# DigitalInput.net
KiCad netlist of a schematic drawn in Altium Designer
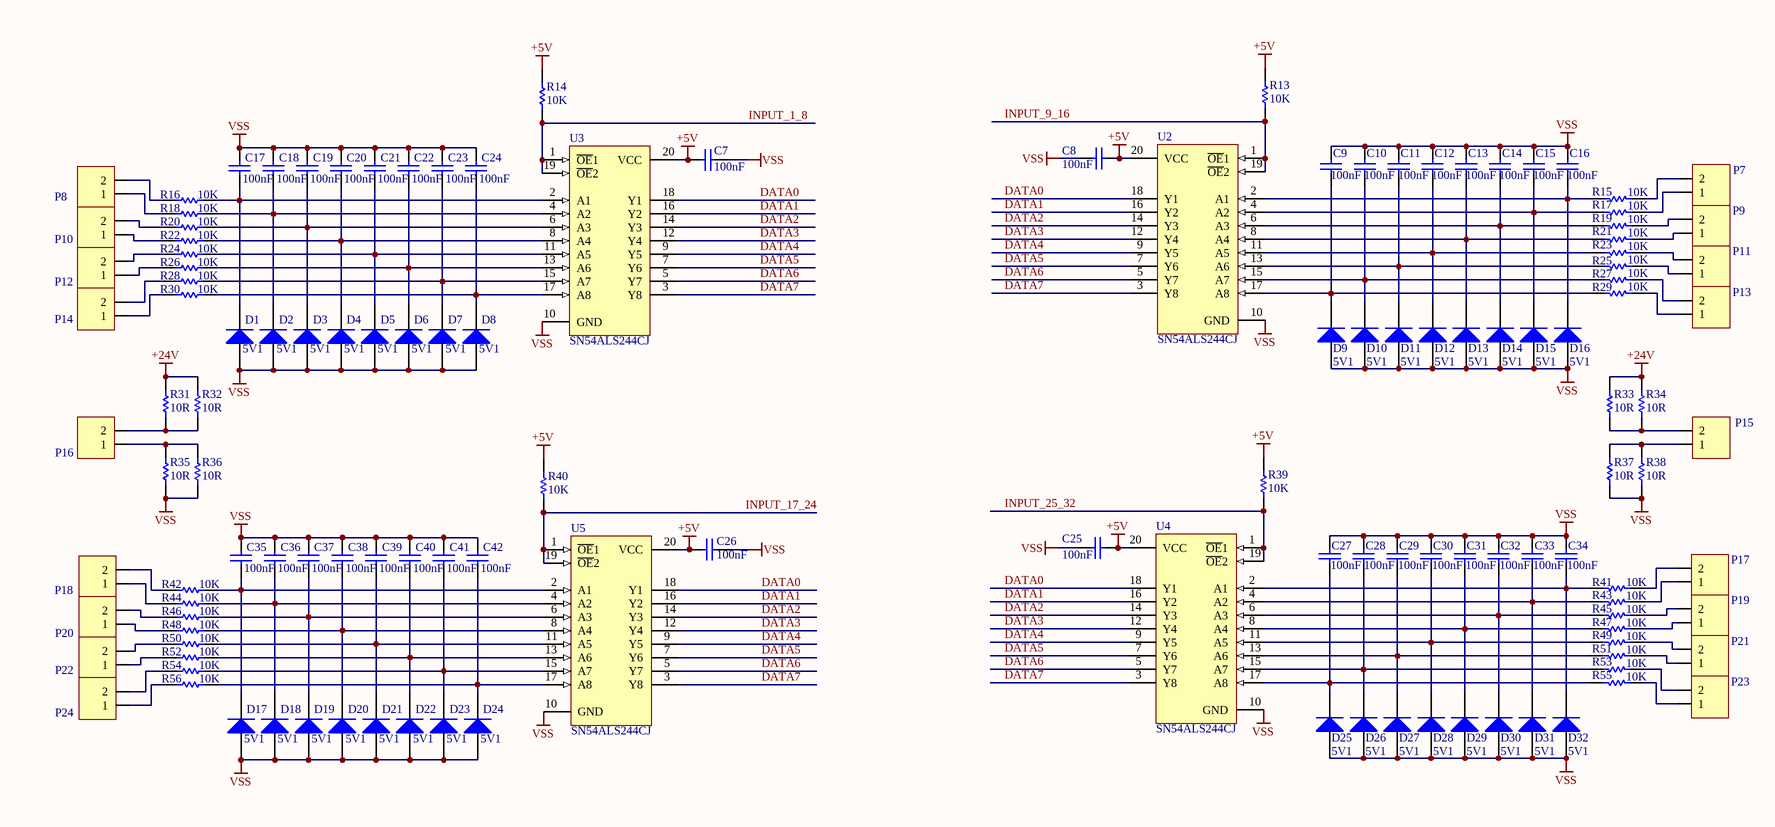
[diagram p0: DigitalInput.SchDoc]

(export (version "E")
  (design (tool "Eeschema 10.0.6"))
  (components
    (comp (ref "C7")
      (value "100nF")
      (footprint "1206")
      (description "Ceramic Chip Capacitor - Standard")
      (fields (field (name "PUBLISHER") "Altium Limited"))
      (libsource (lib "KEMET Chip Capacitor") (part "C1206"))
    )
    (comp (ref "C8")
      (value "100nF")
      (footprint "1206")
      (description "Ceramic Chip Capacitor - Standard")
      (fields (field (name "PUBLISHER") "Altium Limited"))
      (libsource (lib "KEMET Chip Capacitor") (part "C1206"))
    )
    (comp (ref "C9")
      (value "100nF")
      (footprint "1206")
      (description "Ceramic Chip Capacitor - Standard")
      (fields (field (name "PUBLISHER") "Altium Limited"))
      (libsource (lib "KEMET Chip Capacitor") (part "C1206"))
    )
    (comp (ref "C10")
      (value "100nF")
      (footprint "1206")
      (description "Ceramic Chip Capacitor - Standard")
      (fields (field (name "PUBLISHER") "Altium Limited"))
      (libsource (lib "KEMET Chip Capacitor") (part "C1206"))
    )
    (comp (ref "C11")
      (value "100nF")
      (footprint "1206")
      (description "Ceramic Chip Capacitor - Standard")
      (fields (field (name "PUBLISHER") "Altium Limited"))
      (libsource (lib "KEMET Chip Capacitor") (part "C1206"))
    )
    (comp (ref "C12")
      (value "100nF")
      (footprint "1206")
      (description "Ceramic Chip Capacitor - Standard")
      (fields (field (name "PUBLISHER") "Altium Limited"))
      (libsource (lib "KEMET Chip Capacitor") (part "C1206"))
    )
    (comp (ref "C13")
      (value "100nF")
      (footprint "1206")
      (description "Ceramic Chip Capacitor - Standard")
      (fields (field (name "PUBLISHER") "Altium Limited"))
      (libsource (lib "KEMET Chip Capacitor") (part "C1206"))
    )
    (comp (ref "C14")
      (value "100nF")
      (footprint "1206")
      (description "Ceramic Chip Capacitor - Standard")
      (fields (field (name "PUBLISHER") "Altium Limited"))
      (libsource (lib "KEMET Chip Capacitor") (part "C1206"))
    )
    (comp (ref "C15")
      (value "100nF")
      (footprint "1206")
      (description "Ceramic Chip Capacitor - Standard")
      (fields (field (name "PUBLISHER") "Altium Limited"))
      (libsource (lib "KEMET Chip Capacitor") (part "C1206"))
    )
    (comp (ref "C16")
      (value "100nF")
      (footprint "1206")
      (description "Ceramic Chip Capacitor - Standard")
      (fields (field (name "PUBLISHER") "Altium Limited"))
      (libsource (lib "KEMET Chip Capacitor") (part "C1206"))
    )
    (comp (ref "C17")
      (value "100nF")
      (footprint "1206")
      (description "Ceramic Chip Capacitor - Standard")
      (fields (field (name "PUBLISHER") "Altium Limited"))
      (libsource (lib "KEMET Chip Capacitor") (part "C1206"))
    )
    (comp (ref "C18")
      (value "100nF")
      (footprint "1206")
      (description "Ceramic Chip Capacitor - Standard")
      (fields (field (name "PUBLISHER") "Altium Limited"))
      (libsource (lib "KEMET Chip Capacitor") (part "C1206"))
    )
    (comp (ref "C19")
      (value "100nF")
      (footprint "1206")
      (description "Ceramic Chip Capacitor - Standard")
      (fields (field (name "PUBLISHER") "Altium Limited"))
      (libsource (lib "KEMET Chip Capacitor") (part "C1206"))
    )
    (comp (ref "C20")
      (value "100nF")
      (footprint "1206")
      (description "Ceramic Chip Capacitor - Standard")
      (fields (field (name "PUBLISHER") "Altium Limited"))
      (libsource (lib "KEMET Chip Capacitor") (part "C1206"))
    )
    (comp (ref "C21")
      (value "100nF")
      (footprint "1206")
      (description "Ceramic Chip Capacitor - Standard")
      (fields (field (name "PUBLISHER") "Altium Limited"))
      (libsource (lib "KEMET Chip Capacitor") (part "C1206"))
    )
    (comp (ref "C22")
      (value "100nF")
      (footprint "1206")
      (description "Ceramic Chip Capacitor - Standard")
      (fields (field (name "PUBLISHER") "Altium Limited"))
      (libsource (lib "KEMET Chip Capacitor") (part "C1206"))
    )
    (comp (ref "C23")
      (value "100nF")
      (footprint "1206")
      (description "Ceramic Chip Capacitor - Standard")
      (fields (field (name "PUBLISHER") "Altium Limited"))
      (libsource (lib "KEMET Chip Capacitor") (part "C1206"))
    )
    (comp (ref "C24")
      (value "100nF")
      (footprint "1206")
      (description "Ceramic Chip Capacitor - Standard")
      (fields (field (name "PUBLISHER") "Altium Limited"))
      (libsource (lib "KEMET Chip Capacitor") (part "C1206"))
    )
    (comp (ref "C25")
      (value "100nF")
      (footprint "1206")
      (description "Ceramic Chip Capacitor - Standard")
      (fields (field (name "PUBLISHER") "Altium Limited"))
      (libsource (lib "KEMET Chip Capacitor") (part "C1206"))
    )
    (comp (ref "C26")
      (value "100nF")
      (footprint "1206")
      (description "Ceramic Chip Capacitor - Standard")
      (fields (field (name "PUBLISHER") "Altium Limited"))
      (libsource (lib "KEMET Chip Capacitor") (part "C1206"))
    )
    (comp (ref "C27")
      (value "100nF")
      (footprint "1206")
      (description "Ceramic Chip Capacitor - Standard")
      (fields (field (name "PUBLISHER") "Altium Limited"))
      (libsource (lib "KEMET Chip Capacitor") (part "C1206"))
    )
    (comp (ref "C28")
      (value "100nF")
      (footprint "1206")
      (description "Ceramic Chip Capacitor - Standard")
      (fields (field (name "PUBLISHER") "Altium Limited"))
      (libsource (lib "KEMET Chip Capacitor") (part "C1206"))
    )
    (comp (ref "C29")
      (value "100nF")
      (footprint "1206")
      (description "Ceramic Chip Capacitor - Standard")
      (fields (field (name "PUBLISHER") "Altium Limited"))
      (libsource (lib "KEMET Chip Capacitor") (part "C1206"))
    )
    (comp (ref "C30")
      (value "100nF")
      (footprint "1206")
      (description "Ceramic Chip Capacitor - Standard")
      (fields (field (name "PUBLISHER") "Altium Limited"))
      (libsource (lib "KEMET Chip Capacitor") (part "C1206"))
    )
    (comp (ref "C31")
      (value "100nF")
      (footprint "1206")
      (description "Ceramic Chip Capacitor - Standard")
      (fields (field (name "PUBLISHER") "Altium Limited"))
      (libsource (lib "KEMET Chip Capacitor") (part "C1206"))
    )
    (comp (ref "C32")
      (value "100nF")
      (footprint "1206")
      (description "Ceramic Chip Capacitor - Standard")
      (fields (field (name "PUBLISHER") "Altium Limited"))
      (libsource (lib "KEMET Chip Capacitor") (part "C1206"))
    )
    (comp (ref "C33")
      (value "100nF")
      (footprint "1206")
      (description "Ceramic Chip Capacitor - Standard")
      (fields (field (name "PUBLISHER") "Altium Limited"))
      (libsource (lib "KEMET Chip Capacitor") (part "C1206"))
    )
    (comp (ref "C34")
      (value "100nF")
      (footprint "1206")
      (description "Ceramic Chip Capacitor - Standard")
      (fields (field (name "PUBLISHER") "Altium Limited"))
      (libsource (lib "KEMET Chip Capacitor") (part "C1206"))
    )
    (comp (ref "C35")
      (value "100nF")
      (footprint "1206")
      (description "Ceramic Chip Capacitor - Standard")
      (fields (field (name "PUBLISHER") "Altium Limited"))
      (libsource (lib "KEMET Chip Capacitor") (part "C1206"))
    )
    (comp (ref "C36")
      (value "100nF")
      (footprint "1206")
      (description "Ceramic Chip Capacitor - Standard")
      (fields (field (name "PUBLISHER") "Altium Limited"))
      (libsource (lib "KEMET Chip Capacitor") (part "C1206"))
    )
    (comp (ref "C37")
      (value "100nF")
      (footprint "1206")
      (description "Ceramic Chip Capacitor - Standard")
      (fields (field (name "PUBLISHER") "Altium Limited"))
      (libsource (lib "KEMET Chip Capacitor") (part "C1206"))
    )
    (comp (ref "C38")
      (value "100nF")
      (footprint "1206")
      (description "Ceramic Chip Capacitor - Standard")
      (fields (field (name "PUBLISHER") "Altium Limited"))
      (libsource (lib "KEMET Chip Capacitor") (part "C1206"))
    )
    (comp (ref "C39")
      (value "100nF")
      (footprint "1206")
      (description "Ceramic Chip Capacitor - Standard")
      (fields (field (name "PUBLISHER") "Altium Limited"))
      (libsource (lib "KEMET Chip Capacitor") (part "C1206"))
    )
    (comp (ref "C40")
      (value "100nF")
      (footprint "1206")
      (description "Ceramic Chip Capacitor - Standard")
      (fields (field (name "PUBLISHER") "Altium Limited"))
      (libsource (lib "KEMET Chip Capacitor") (part "C1206"))
    )
    (comp (ref "C41")
      (value "100nF")
      (footprint "1206")
      (description "Ceramic Chip Capacitor - Standard")
      (fields (field (name "PUBLISHER") "Altium Limited"))
      (libsource (lib "KEMET Chip Capacitor") (part "C1206"))
    )
    (comp (ref "C42")
      (value "100nF")
      (footprint "1206")
      (description "Ceramic Chip Capacitor - Standard")
      (fields (field (name "PUBLISHER") "Altium Limited"))
      (libsource (lib "KEMET Chip Capacitor") (part "C1206"))
    )
    (comp (ref "D1")
      (value "5V1")
      (footprint "SOD80C")
      (description "Voltage Regulator Diode")
      (fields (field (name "PUBLISHER") "Altium Limited"))
      (libsource (lib "Philips Discrete Diode - Switching") (part "BZV85-C5V1"))
    )
    (comp (ref "D2")
      (value "5V1")
      (footprint "SOD80C")
      (description "Voltage Regulator Diode")
      (fields (field (name "PUBLISHER") "Altium Limited"))
      (libsource (lib "Philips Discrete Diode - Switching") (part "BZV85-C5V1"))
    )
    (comp (ref "D3")
      (value "5V1")
      (footprint "SOD80C")
      (description "Voltage Regulator Diode")
      (fields (field (name "PUBLISHER") "Altium Limited"))
      (libsource (lib "Philips Discrete Diode - Switching") (part "BZV85-C5V1"))
    )
    (comp (ref "D4")
      (value "5V1")
      (footprint "SOD80C")
      (description "Voltage Regulator Diode")
      (fields (field (name "PUBLISHER") "Altium Limited"))
      (libsource (lib "Philips Discrete Diode - Switching") (part "BZV85-C5V1"))
    )
    (comp (ref "D5")
      (value "5V1")
      (footprint "SOD80C")
      (description "Voltage Regulator Diode")
      (fields (field (name "PUBLISHER") "Altium Limited"))
      (libsource (lib "Philips Discrete Diode - Switching") (part "BZV85-C5V1"))
    )
    (comp (ref "D6")
      (value "5V1")
      (footprint "SOD80C")
      (description "Voltage Regulator Diode")
      (fields (field (name "PUBLISHER") "Altium Limited"))
      (libsource (lib "Philips Discrete Diode - Switching") (part "BZV85-C5V1"))
    )
    (comp (ref "D7")
      (value "5V1")
      (footprint "SOD80C")
      (description "Voltage Regulator Diode")
      (fields (field (name "PUBLISHER") "Altium Limited"))
      (libsource (lib "Philips Discrete Diode - Switching") (part "BZV85-C5V1"))
    )
    (comp (ref "D8")
      (value "5V1")
      (footprint "SOD80C")
      (description "Voltage Regulator Diode")
      (fields (field (name "PUBLISHER") "Altium Limited"))
      (libsource (lib "Philips Discrete Diode - Switching") (part "BZV85-C5V1"))
    )
    (comp (ref "D9")
      (value "5V1")
      (footprint "SOD80C")
      (description "Voltage Regulator Diode")
      (fields (field (name "PUBLISHER") "Altium Limited"))
      (libsource (lib "Philips Discrete Diode - Switching") (part "BZV85-C5V1"))
    )
    (comp (ref "D10")
      (value "5V1")
      (footprint "SOD80C")
      (description "Voltage Regulator Diode")
      (fields (field (name "PUBLISHER") "Altium Limited"))
      (libsource (lib "Philips Discrete Diode - Switching") (part "BZV85-C5V1"))
    )
    (comp (ref "D11")
      (value "5V1")
      (footprint "SOD80C")
      (description "Voltage Regulator Diode")
      (fields (field (name "PUBLISHER") "Altium Limited"))
      (libsource (lib "Philips Discrete Diode - Switching") (part "BZV85-C5V1"))
    )
    (comp (ref "D12")
      (value "5V1")
      (footprint "SOD80C")
      (description "Voltage Regulator Diode")
      (fields (field (name "PUBLISHER") "Altium Limited"))
      (libsource (lib "Philips Discrete Diode - Switching") (part "BZV85-C5V1"))
    )
    (comp (ref "D13")
      (value "5V1")
      (footprint "SOD80C")
      (description "Voltage Regulator Diode")
      (fields (field (name "PUBLISHER") "Altium Limited"))
      (libsource (lib "Philips Discrete Diode - Switching") (part "BZV85-C5V1"))
    )
    (comp (ref "D14")
      (value "5V1")
      (footprint "SOD80C")
      (description "Voltage Regulator Diode")
      (fields (field (name "PUBLISHER") "Altium Limited"))
      (libsource (lib "Philips Discrete Diode - Switching") (part "BZV85-C5V1"))
    )
    (comp (ref "D15")
      (value "5V1")
      (footprint "SOD80C")
      (description "Voltage Regulator Diode")
      (fields (field (name "PUBLISHER") "Altium Limited"))
      (libsource (lib "Philips Discrete Diode - Switching") (part "BZV85-C5V1"))
    )
    (comp (ref "D16")
      (value "5V1")
      (footprint "SOD80C")
      (description "Voltage Regulator Diode")
      (fields (field (name "PUBLISHER") "Altium Limited"))
      (libsource (lib "Philips Discrete Diode - Switching") (part "BZV85-C5V1"))
    )
    (comp (ref "D17")
      (value "5V1")
      (footprint "SOD80C")
      (description "Voltage Regulator Diode")
      (fields (field (name "PUBLISHER") "Altium Limited"))
      (libsource (lib "Philips Discrete Diode - Switching") (part "BZV85-C5V1"))
    )
    (comp (ref "D18")
      (value "5V1")
      (footprint "SOD80C")
      (description "Voltage Regulator Diode")
      (fields (field (name "PUBLISHER") "Altium Limited"))
      (libsource (lib "Philips Discrete Diode - Switching") (part "BZV85-C5V1"))
    )
    (comp (ref "D19")
      (value "5V1")
      (footprint "SOD80C")
      (description "Voltage Regulator Diode")
      (fields (field (name "PUBLISHER") "Altium Limited"))
      (libsource (lib "Philips Discrete Diode - Switching") (part "BZV85-C5V1"))
    )
    (comp (ref "D20")
      (value "5V1")
      (footprint "SOD80C")
      (description "Voltage Regulator Diode")
      (fields (field (name "PUBLISHER") "Altium Limited"))
      (libsource (lib "Philips Discrete Diode - Switching") (part "BZV85-C5V1"))
    )
    (comp (ref "D21")
      (value "5V1")
      (footprint "SOD80C")
      (description "Voltage Regulator Diode")
      (fields (field (name "PUBLISHER") "Altium Limited"))
      (libsource (lib "Philips Discrete Diode - Switching") (part "BZV85-C5V1"))
    )
    (comp (ref "D22")
      (value "5V1")
      (footprint "SOD80C")
      (description "Voltage Regulator Diode")
      (fields (field (name "PUBLISHER") "Altium Limited"))
      (libsource (lib "Philips Discrete Diode - Switching") (part "BZV85-C5V1"))
    )
    (comp (ref "D23")
      (value "5V1")
      (footprint "SOD80C")
      (description "Voltage Regulator Diode")
      (fields (field (name "PUBLISHER") "Altium Limited"))
      (libsource (lib "Philips Discrete Diode - Switching") (part "BZV85-C5V1"))
    )
    (comp (ref "D24")
      (value "5V1")
      (footprint "SOD80C")
      (description "Voltage Regulator Diode")
      (fields (field (name "PUBLISHER") "Altium Limited"))
      (libsource (lib "Philips Discrete Diode - Switching") (part "BZV85-C5V1"))
    )
    (comp (ref "D25")
      (value "5V1")
      (footprint "SOD80C")
      (description "Voltage Regulator Diode")
      (fields (field (name "PUBLISHER") "Altium Limited"))
      (libsource (lib "Philips Discrete Diode - Switching") (part "BZV85-C5V1"))
    )
    (comp (ref "D26")
      (value "5V1")
      (footprint "SOD80C")
      (description "Voltage Regulator Diode")
      (fields (field (name "PUBLISHER") "Altium Limited"))
      (libsource (lib "Philips Discrete Diode - Switching") (part "BZV85-C5V1"))
    )
    (comp (ref "D27")
      (value "5V1")
      (footprint "SOD80C")
      (description "Voltage Regulator Diode")
      (fields (field (name "PUBLISHER") "Altium Limited"))
      (libsource (lib "Philips Discrete Diode - Switching") (part "BZV85-C5V1"))
    )
    (comp (ref "D28")
      (value "5V1")
      (footprint "SOD80C")
      (description "Voltage Regulator Diode")
      (fields (field (name "PUBLISHER") "Altium Limited"))
      (libsource (lib "Philips Discrete Diode - Switching") (part "BZV85-C5V1"))
    )
    (comp (ref "D29")
      (value "5V1")
      (footprint "SOD80C")
      (description "Voltage Regulator Diode")
      (fields (field (name "PUBLISHER") "Altium Limited"))
      (libsource (lib "Philips Discrete Diode - Switching") (part "BZV85-C5V1"))
    )
    (comp (ref "D30")
      (value "5V1")
      (footprint "SOD80C")
      (description "Voltage Regulator Diode")
      (fields (field (name "PUBLISHER") "Altium Limited"))
      (libsource (lib "Philips Discrete Diode - Switching") (part "BZV85-C5V1"))
    )
    (comp (ref "D31")
      (value "5V1")
      (footprint "SOD80C")
      (description "Voltage Regulator Diode")
      (fields (field (name "PUBLISHER") "Altium Limited"))
      (libsource (lib "Philips Discrete Diode - Switching") (part "BZV85-C5V1"))
    )
    (comp (ref "D32")
      (value "5V1")
      (footprint "SOD80C")
      (description "Voltage Regulator Diode")
      (fields (field (name "PUBLISHER") "Altium Limited"))
      (libsource (lib "Philips Discrete Diode - Switching") (part "BZV85-C5V1"))
    )
    (comp (ref "P7")
      (value "~")
      (footprint "TERMINAL BLOK 2")
      (description "Terminal blok 2")
      (libsource (lib "") (part "Terminal blok 2 pina_3"))
    )
    (comp (ref "P8")
      (value "~")
      (footprint "TERMINAL BLOK 2")
      (description "Terminal blok 2")
      (libsource (lib "TERMINAL_CONNECOR_2") (part "Terminal blok 2 pina"))
    )
    (comp (ref "P9")
      (value "~")
      (footprint "TERMINAL BLOK 2")
      (description "Terminal blok 2")
      (libsource (lib "") (part "Terminal blok 2 pina_1"))
    )
    (comp (ref "P10")
      (value "~")
      (footprint "TERMINAL BLOK 2")
      (description "Terminal blok 2")
      (libsource (lib "TERMINAL_CONNECOR_2") (part "Terminal blok 2 pina"))
    )
    (comp (ref "P11")
      (value "~")
      (footprint "TERMINAL BLOK 2")
      (description "Terminal blok 2")
      (libsource (lib "") (part "Terminal blok 2 pina_2"))
    )
    (comp (ref "P12")
      (value "~")
      (footprint "TERMINAL BLOK 2")
      (description "Terminal blok 2")
      (libsource (lib "") (part "Terminal blok 2 pina_5"))
    )
    (comp (ref "P13")
      (value "~")
      (footprint "TERMINAL BLOK 2")
      (description "Terminal blok 2")
      (libsource (lib "") (part "Terminal blok 2 pina_2"))
    )
    (comp (ref "P14")
      (value "~")
      (footprint "TERMINAL BLOK 2")
      (description "Terminal blok 2")
      (libsource (lib "") (part "Terminal blok 2 pina_7"))
    )
    (comp (ref "P15")
      (value "~")
      (footprint "TERMINAL BLOK 2")
      (description "Terminal blok 2")
      (libsource (lib "") (part "Terminal blok 2 pina_6"))
    )
    (comp (ref "P16")
      (value "~")
      (footprint "TERMINAL BLOK 2")
      (description "Terminal blok 2")
      (libsource (lib "") (part "Terminal blok 2 pina_8"))
    )
    (comp (ref "P17")
      (value "~")
      (footprint "TERMINAL BLOK 2")
      (description "Terminal blok 2")
      (libsource (lib "") (part "Terminal blok 2 pina_1"))
    )
    (comp (ref "P18")
      (value "~")
      (footprint "TERMINAL BLOK 2")
      (description "Terminal blok 2")
      (libsource (lib "TERMINAL_CONNECOR_2") (part "Terminal blok 2 pina"))
    )
    (comp (ref "P19")
      (value "~")
      (footprint "TERMINAL BLOK 2")
      (description "Terminal blok 2")
      (libsource (lib "") (part "Terminal blok 2 pina_1"))
    )
    (comp (ref "P20")
      (value "~")
      (footprint "TERMINAL BLOK 2")
      (description "Terminal blok 2")
      (libsource (lib "") (part "Terminal blok 2 pina_5"))
    )
    (comp (ref "P21")
      (value "~")
      (footprint "TERMINAL BLOK 2")
      (description "Terminal blok 2")
      (libsource (lib "") (part "Terminal blok 2 pina_2"))
    )
    (comp (ref "P22")
      (value "~")
      (footprint "TERMINAL BLOK 2")
      (description "Terminal blok 2")
      (libsource (lib "") (part "Terminal blok 2 pina_5"))
    )
    (comp (ref "P23")
      (value "~")
      (footprint "TERMINAL BLOK 2")
      (description "Terminal blok 2")
      (libsource (lib "") (part "Terminal blok 2 pina_3"))
    )
    (comp (ref "P24")
      (value "~")
      (footprint "TERMINAL BLOK 2")
      (description "Terminal blok 2")
      (libsource (lib "") (part "Terminal blok 2 pina_4"))
    )
    (comp (ref "R13")
      (value "10K")
      (footprint "ERA-0805")
      (fields (field (name "PUBLISHER") "Altium Limited"))
      (libsource (lib "Panasonic Resistor") (part "ERA6Y"))
    )
    (comp (ref "R14")
      (value "10K")
      (footprint "ERA-0805")
      (fields (field (name "PUBLISHER") "Altium Limited"))
      (libsource (lib "Panasonic Resistor") (part "ERA6Y"))
    )
    (comp (ref "R15")
      (value "10K")
      (footprint "ERA-0805")
      (fields (field (name "PUBLISHER") "Altium Limited"))
      (libsource (lib "Panasonic Resistor") (part "ERA6Y"))
    )
    (comp (ref "R16")
      (value "10K")
      (footprint "ERA-0805")
      (fields (field (name "PUBLISHER") "Altium Limited"))
      (libsource (lib "Panasonic Resistor") (part "ERA6Y"))
    )
    (comp (ref "R17")
      (value "10K")
      (footprint "ERA-0805")
      (fields (field (name "PUBLISHER") "Altium Limited"))
      (libsource (lib "Panasonic Resistor") (part "ERA6Y"))
    )
    (comp (ref "R18")
      (value "10K")
      (footprint "ERA-0805")
      (fields (field (name "PUBLISHER") "Altium Limited"))
      (libsource (lib "Panasonic Resistor") (part "ERA6Y"))
    )
    (comp (ref "R19")
      (value "10K")
      (footprint "ERA-0805")
      (fields (field (name "PUBLISHER") "Altium Limited"))
      (libsource (lib "Panasonic Resistor") (part "ERA6Y"))
    )
    (comp (ref "R20")
      (value "10K")
      (footprint "ERA-0805")
      (fields (field (name "PUBLISHER") "Altium Limited"))
      (libsource (lib "Panasonic Resistor") (part "ERA6Y"))
    )
    (comp (ref "R21")
      (value "10K")
      (footprint "ERA-0805")
      (fields (field (name "PUBLISHER") "Altium Limited"))
      (libsource (lib "Panasonic Resistor") (part "ERA6Y"))
    )
    (comp (ref "R22")
      (value "10K")
      (footprint "ERA-0805")
      (fields (field (name "PUBLISHER") "Altium Limited"))
      (libsource (lib "Panasonic Resistor") (part "ERA6Y"))
    )
    (comp (ref "R23")
      (value "10K")
      (footprint "ERA-0805")
      (fields (field (name "PUBLISHER") "Altium Limited"))
      (libsource (lib "Panasonic Resistor") (part "ERA6Y"))
    )
    (comp (ref "R24")
      (value "10K")
      (footprint "ERA-0805")
      (fields (field (name "PUBLISHER") "Altium Limited"))
      (libsource (lib "Panasonic Resistor") (part "ERA6Y"))
    )
    (comp (ref "R25")
      (value "10K")
      (footprint "ERA-0805")
      (fields (field (name "PUBLISHER") "Altium Limited"))
      (libsource (lib "Panasonic Resistor") (part "ERA6Y"))
    )
    (comp (ref "R26")
      (value "10K")
      (footprint "ERA-0805")
      (fields (field (name "PUBLISHER") "Altium Limited"))
      (libsource (lib "Panasonic Resistor") (part "ERA6Y"))
    )
    (comp (ref "R27")
      (value "10K")
      (footprint "ERA-0805")
      (fields (field (name "PUBLISHER") "Altium Limited"))
      (libsource (lib "Panasonic Resistor") (part "ERA6Y"))
    )
    (comp (ref "R28")
      (value "10K")
      (footprint "ERA-0805")
      (fields (field (name "PUBLISHER") "Altium Limited"))
      (libsource (lib "Panasonic Resistor") (part "ERA6Y"))
    )
    (comp (ref "R29")
      (value "10K")
      (footprint "ERA-0805")
      (fields (field (name "PUBLISHER") "Altium Limited"))
      (libsource (lib "Panasonic Resistor") (part "ERA6Y"))
    )
    (comp (ref "R30")
      (value "10K")
      (footprint "ERA-0805")
      (fields (field (name "PUBLISHER") "Altium Limited"))
      (libsource (lib "Panasonic Resistor") (part "ERA6Y"))
    )
    (comp (ref "R31")
      (value "10R")
      (footprint "ERA-0603")
      (fields (field (name "PUBLISHER") "Altium Limited"))
      (libsource (lib "Panasonic Resistor") (part "ERA3Y"))
    )
    (comp (ref "R32")
      (value "10R")
      (footprint "ERA-0603")
      (fields (field (name "PUBLISHER") "Altium Limited"))
      (libsource (lib "Panasonic Resistor") (part "ERA3Y"))
    )
    (comp (ref "R33")
      (value "10R")
      (footprint "ERA-0603")
      (fields (field (name "PUBLISHER") "Altium Limited"))
      (libsource (lib "Panasonic Resistor") (part "ERA3Y"))
    )
    (comp (ref "R34")
      (value "10R")
      (footprint "ERA-0603")
      (fields (field (name "PUBLISHER") "Altium Limited"))
      (libsource (lib "Panasonic Resistor") (part "ERA3Y"))
    )
    (comp (ref "R35")
      (value "10R")
      (footprint "ERA-0603")
      (fields (field (name "PUBLISHER") "Altium Limited"))
      (libsource (lib "Panasonic Resistor") (part "ERA3Y"))
    )
    (comp (ref "R36")
      (value "10R")
      (footprint "ERA-0603")
      (fields (field (name "PUBLISHER") "Altium Limited"))
      (libsource (lib "Panasonic Resistor") (part "ERA3Y"))
    )
    (comp (ref "R37")
      (value "10R")
      (footprint "ERA-0603")
      (fields (field (name "PUBLISHER") "Altium Limited"))
      (libsource (lib "Panasonic Resistor") (part "ERA3Y"))
    )
    (comp (ref "R38")
      (value "10R")
      (footprint "ERA-0603")
      (fields (field (name "PUBLISHER") "Altium Limited"))
      (libsource (lib "Panasonic Resistor") (part "ERA3Y"))
    )
    (comp (ref "R39")
      (value "10K")
      (footprint "ERA-0805")
      (fields (field (name "PUBLISHER") "Altium Limited"))
      (libsource (lib "Panasonic Resistor") (part "ERA6Y"))
    )
    (comp (ref "R40")
      (value "10K")
      (footprint "ERA-0805")
      (fields (field (name "PUBLISHER") "Altium Limited"))
      (libsource (lib "Panasonic Resistor") (part "ERA6Y"))
    )
    (comp (ref "R41")
      (value "10K")
      (footprint "ERA-0805")
      (fields (field (name "PUBLISHER") "Altium Limited"))
      (libsource (lib "Panasonic Resistor") (part "ERA6Y"))
    )
    (comp (ref "R42")
      (value "10K")
      (footprint "ERA-0805")
      (fields (field (name "PUBLISHER") "Altium Limited"))
      (libsource (lib "Panasonic Resistor") (part "ERA6Y"))
    )
    (comp (ref "R43")
      (value "10K")
      (footprint "ERA-0805")
      (fields (field (name "PUBLISHER") "Altium Limited"))
      (libsource (lib "Panasonic Resistor") (part "ERA6Y"))
    )
    (comp (ref "R44")
      (value "10K")
      (footprint "ERA-0805")
      (fields (field (name "PUBLISHER") "Altium Limited"))
      (libsource (lib "Panasonic Resistor") (part "ERA6Y"))
    )
    (comp (ref "R45")
      (value "10K")
      (footprint "ERA-0805")
      (fields (field (name "PUBLISHER") "Altium Limited"))
      (libsource (lib "Panasonic Resistor") (part "ERA6Y"))
    )
    (comp (ref "R46")
      (value "10K")
      (footprint "ERA-0805")
      (fields (field (name "PUBLISHER") "Altium Limited"))
      (libsource (lib "Panasonic Resistor") (part "ERA6Y"))
    )
    (comp (ref "R47")
      (value "10K")
      (footprint "ERA-0805")
      (fields (field (name "PUBLISHER") "Altium Limited"))
      (libsource (lib "Panasonic Resistor") (part "ERA6Y"))
    )
    (comp (ref "R48")
      (value "10K")
      (footprint "ERA-0805")
      (fields (field (name "PUBLISHER") "Altium Limited"))
      (libsource (lib "Panasonic Resistor") (part "ERA6Y"))
    )
    (comp (ref "R49")
      (value "10K")
      (footprint "ERA-0805")
      (fields (field (name "PUBLISHER") "Altium Limited"))
      (libsource (lib "Panasonic Resistor") (part "ERA6Y"))
    )
    (comp (ref "R50")
      (value "10K")
      (footprint "ERA-0805")
      (fields (field (name "PUBLISHER") "Altium Limited"))
      (libsource (lib "Panasonic Resistor") (part "ERA6Y"))
    )
    (comp (ref "R51")
      (value "10K")
      (footprint "ERA-0805")
      (fields (field (name "PUBLISHER") "Altium Limited"))
      (libsource (lib "Panasonic Resistor") (part "ERA6Y"))
    )
    (comp (ref "R52")
      (value "10K")
      (footprint "ERA-0805")
      (fields (field (name "PUBLISHER") "Altium Limited"))
      (libsource (lib "Panasonic Resistor") (part "ERA6Y"))
    )
    (comp (ref "R53")
      (value "10K")
      (footprint "ERA-0805")
      (fields (field (name "PUBLISHER") "Altium Limited"))
      (libsource (lib "Panasonic Resistor") (part "ERA6Y"))
    )
    (comp (ref "R54")
      (value "10K")
      (footprint "ERA-0805")
      (fields (field (name "PUBLISHER") "Altium Limited"))
      (libsource (lib "Panasonic Resistor") (part "ERA6Y"))
    )
    (comp (ref "R55")
      (value "10K")
      (footprint "ERA-0805")
      (fields (field (name "PUBLISHER") "Altium Limited"))
      (libsource (lib "Panasonic Resistor") (part "ERA6Y"))
    )
    (comp (ref "R56")
      (value "10K")
      (footprint "ERA-0805")
      (fields (field (name "PUBLISHER") "Altium Limited"))
      (libsource (lib "Panasonic Resistor") (part "ERA6Y"))
    )
    (comp (ref "U2")
      (value "SN54ALS244CJ")
      (footprint "J020")
      (description "Octal Buffer/Driver with 3-State Outputs")
      (fields (field (name "PUBLISHER") "Altium Limited"))
      (libsource (lib "") (part "SN54ALS244CJ_1"))
    )
    (comp (ref "U3")
      (value "SN54ALS244CJ")
      (footprint "J020")
      (description "Octal Buffer/Driver with 3-State Outputs")
      (fields (field (name "PUBLISHER") "Altium Limited"))
      (libsource (lib "TI Logic Buffer Line Driver") (part "SN54ALS244CJ"))
    )
    (comp (ref "U4")
      (value "SN54ALS244CJ")
      (footprint "J020")
      (description "Octal Buffer/Driver with 3-State Outputs")
      (fields (field (name "PUBLISHER") "Altium Limited"))
      (libsource (lib "") (part "SN54ALS244CJ_1"))
    )
    (comp (ref "U5")
      (value "SN54ALS244CJ")
      (footprint "J020")
      (description "Octal Buffer/Driver with 3-State Outputs")
      (fields (field (name "PUBLISHER") "Altium Limited"))
      (libsource (lib "TI Logic Buffer Line Driver") (part "SN54ALS244CJ"))
    )
  )
  (nets
    (net (code "1") (name "+5V") (class "Default")
      (node (ref "C25") (pin "1") (pinfunction "1_1") (pintype "passive"))
      (node (ref "C26") (pin "1") (pinfunction "1_1") (pintype "passive"))
      (node (ref "C7") (pin "1") (pinfunction "1_1") (pintype "passive"))
      (node (ref "C8") (pin "1") (pinfunction "1_1") (pintype "passive"))
      (node (ref "R13") (pin "2") (pinfunction "2_2") (pintype "passive"))
      (node (ref "R14") (pin "2") (pinfunction "2_2") (pintype "passive"))
      (node (ref "R39") (pin "2") (pinfunction "2_2") (pintype "passive"))
      (node (ref "R40") (pin "2") (pinfunction "2_2") (pintype "passive"))
      (node (ref "U2") (pin "20") (pinfunction "VCC_20") (pintype "power_in"))
      (node (ref "U3") (pin "20") (pinfunction "VCC_20") (pintype "power_in"))
      (node (ref "U4") (pin "20") (pinfunction "VCC_20") (pintype "power_in"))
      (node (ref "U5") (pin "20") (pinfunction "VCC_20") (pintype "power_in"))
    )
    (net (code "2") (name "+24V") (class "Default")
      (node (ref "R31") (pin "2") (pinfunction "2_2") (pintype "passive"))
      (node (ref "R32") (pin "2") (pinfunction "2_2") (pintype "passive"))
      (node (ref "R33") (pin "2") (pinfunction "2_2") (pintype "passive"))
      (node (ref "R34") (pin "2") (pinfunction "2_2") (pintype "passive"))
    )
    (net (code "3") (name "/DATA0") (class "Default")
      (node (ref "U2") (pin "18") (pinfunction "Y1_18") (pintype "tri_state"))
      (node (ref "U3") (pin "18") (pinfunction "Y1_18") (pintype "tri_state"))
      (node (ref "U4") (pin "18") (pinfunction "Y1_18") (pintype "tri_state"))
      (node (ref "U5") (pin "18") (pinfunction "Y1_18") (pintype "tri_state"))
    )
    (net (code "4") (name "/DATA1") (class "Default")
      (node (ref "U2") (pin "16") (pinfunction "Y2_16") (pintype "tri_state"))
      (node (ref "U3") (pin "16") (pinfunction "Y2_16") (pintype "tri_state"))
      (node (ref "U4") (pin "16") (pinfunction "Y2_16") (pintype "tri_state"))
      (node (ref "U5") (pin "16") (pinfunction "Y2_16") (pintype "tri_state"))
    )
    (net (code "5") (name "/DATA2") (class "Default")
      (node (ref "U2") (pin "14") (pinfunction "Y3_14") (pintype "tri_state"))
      (node (ref "U3") (pin "14") (pinfunction "Y3_14") (pintype "tri_state"))
      (node (ref "U4") (pin "14") (pinfunction "Y3_14") (pintype "tri_state"))
      (node (ref "U5") (pin "14") (pinfunction "Y3_14") (pintype "tri_state"))
    )
    (net (code "6") (name "/DATA3") (class "Default")
      (node (ref "U2") (pin "12") (pinfunction "Y4_12") (pintype "tri_state"))
      (node (ref "U3") (pin "12") (pinfunction "Y4_12") (pintype "tri_state"))
      (node (ref "U4") (pin "12") (pinfunction "Y4_12") (pintype "tri_state"))
      (node (ref "U5") (pin "12") (pinfunction "Y4_12") (pintype "tri_state"))
    )
    (net (code "7") (name "/DATA4") (class "Default")
      (node (ref "U2") (pin "9") (pinfunction "Y5_9") (pintype "tri_state"))
      (node (ref "U3") (pin "9") (pinfunction "Y5_9") (pintype "tri_state"))
      (node (ref "U4") (pin "9") (pinfunction "Y5_9") (pintype "tri_state"))
      (node (ref "U5") (pin "9") (pinfunction "Y5_9") (pintype "tri_state"))
    )
    (net (code "8") (name "/DATA5") (class "Default")
      (node (ref "U2") (pin "7") (pinfunction "Y6_7") (pintype "tri_state"))
      (node (ref "U3") (pin "7") (pinfunction "Y6_7") (pintype "tri_state"))
      (node (ref "U4") (pin "7") (pinfunction "Y6_7") (pintype "tri_state"))
      (node (ref "U5") (pin "7") (pinfunction "Y6_7") (pintype "tri_state"))
    )
    (net (code "9") (name "/DATA6") (class "Default")
      (node (ref "U2") (pin "5") (pinfunction "Y7_5") (pintype "tri_state"))
      (node (ref "U3") (pin "5") (pinfunction "Y7_5") (pintype "tri_state"))
      (node (ref "U4") (pin "5") (pinfunction "Y7_5") (pintype "tri_state"))
      (node (ref "U5") (pin "5") (pinfunction "Y7_5") (pintype "tri_state"))
    )
    (net (code "10") (name "/DATA7") (class "Default")
      (node (ref "U2") (pin "3") (pinfunction "Y8_3") (pintype "tri_state"))
      (node (ref "U3") (pin "3") (pinfunction "Y8_3") (pintype "tri_state"))
      (node (ref "U4") (pin "3") (pinfunction "Y8_3") (pintype "tri_state"))
      (node (ref "U5") (pin "3") (pinfunction "Y8_3") (pintype "tri_state"))
    )
    (net (code "11") (name "/INPUT_1_8") (class "Default")
      (node (ref "R14") (pin "1") (pinfunction "1_1") (pintype "passive"))
      (node (ref "U3") (pin "1") (pinfunction "~{OE}1_1") (pintype "input"))
      (node (ref "U3") (pin "19") (pinfunction "~{OE}2_19") (pintype "input"))
    )
    (net (code "12") (name "/INPUT_9_16") (class "Default")
      (node (ref "R13") (pin "1") (pinfunction "1_1") (pintype "passive"))
      (node (ref "U2") (pin "1") (pinfunction "~{OE}1_1") (pintype "input"))
      (node (ref "U2") (pin "19") (pinfunction "~{OE}2_19") (pintype "input"))
    )
    (net (code "13") (name "/INPUT_17_24") (class "Default")
      (node (ref "R40") (pin "1") (pinfunction "1_1") (pintype "passive"))
      (node (ref "U5") (pin "1") (pinfunction "~{OE}1_1") (pintype "input"))
      (node (ref "U5") (pin "19") (pinfunction "~{OE}2_19") (pintype "input"))
    )
    (net (code "14") (name "/INPUT_25_32") (class "Default")
      (node (ref "R39") (pin "1") (pinfunction "1_1") (pintype "passive"))
      (node (ref "U4") (pin "1") (pinfunction "~{OE}1_1") (pintype "input"))
      (node (ref "U4") (pin "19") (pinfunction "~{OE}2_19") (pintype "input"))
    )
    (net (code "15") (name "Net-(D1-K)") (class "Default")
      (node (ref "C17") (pin "1") (pinfunction "1_1") (pintype "passive"))
      (node (ref "D1") (pin "2") (pinfunction "K_2") (pintype "passive"))
      (node (ref "R16") (pin "2") (pinfunction "2_2") (pintype "passive"))
      (node (ref "U3") (pin "2") (pinfunction "A1_2") (pintype "input"))
    )
    (net (code "16") (name "Net-(D2-K)") (class "Default")
      (node (ref "C18") (pin "1") (pinfunction "1_1") (pintype "passive"))
      (node (ref "D2") (pin "2") (pinfunction "K_2") (pintype "passive"))
      (node (ref "R18") (pin "2") (pinfunction "2_2") (pintype "passive"))
      (node (ref "U3") (pin "4") (pinfunction "A2_4") (pintype "input"))
    )
    (net (code "17") (name "Net-(D3-K)") (class "Default")
      (node (ref "C19") (pin "1") (pinfunction "1_1") (pintype "passive"))
      (node (ref "D3") (pin "2") (pinfunction "K_2") (pintype "passive"))
      (node (ref "R20") (pin "2") (pinfunction "2_2") (pintype "passive"))
      (node (ref "U3") (pin "6") (pinfunction "A3_6") (pintype "input"))
    )
    (net (code "18") (name "Net-(D4-K)") (class "Default")
      (node (ref "C20") (pin "1") (pinfunction "1_1") (pintype "passive"))
      (node (ref "D4") (pin "2") (pinfunction "K_2") (pintype "passive"))
      (node (ref "R22") (pin "2") (pinfunction "2_2") (pintype "passive"))
      (node (ref "U3") (pin "8") (pinfunction "A4_8") (pintype "input"))
    )
    (net (code "19") (name "Net-(D5-K)") (class "Default")
      (node (ref "C21") (pin "1") (pinfunction "1_1") (pintype "passive"))
      (node (ref "D5") (pin "2") (pinfunction "K_2") (pintype "passive"))
      (node (ref "R24") (pin "2") (pinfunction "2_2") (pintype "passive"))
      (node (ref "U3") (pin "11") (pinfunction "A5_11") (pintype "input"))
    )
    (net (code "20") (name "Net-(D6-K)") (class "Default")
      (node (ref "C22") (pin "1") (pinfunction "1_1") (pintype "passive"))
      (node (ref "D6") (pin "2") (pinfunction "K_2") (pintype "passive"))
      (node (ref "R26") (pin "2") (pinfunction "2_2") (pintype "passive"))
      (node (ref "U3") (pin "13") (pinfunction "A6_13") (pintype "input"))
    )
    (net (code "21") (name "Net-(D7-K)") (class "Default")
      (node (ref "C23") (pin "1") (pinfunction "1_1") (pintype "passive"))
      (node (ref "D7") (pin "2") (pinfunction "K_2") (pintype "passive"))
      (node (ref "R28") (pin "2") (pinfunction "2_2") (pintype "passive"))
      (node (ref "U3") (pin "15") (pinfunction "A7_15") (pintype "input"))
    )
    (net (code "22") (name "Net-(D8-K)") (class "Default")
      (node (ref "C24") (pin "1") (pinfunction "1_1") (pintype "passive"))
      (node (ref "D8") (pin "2") (pinfunction "K_2") (pintype "passive"))
      (node (ref "R30") (pin "2") (pinfunction "2_2") (pintype "passive"))
      (node (ref "U3") (pin "17") (pinfunction "A8_17") (pintype "input"))
    )
    (net (code "23") (name "Net-(D9-K)") (class "Default")
      (node (ref "C9") (pin "1") (pinfunction "1_1") (pintype "passive"))
      (node (ref "D9") (pin "2") (pinfunction "K_2") (pintype "passive"))
      (node (ref "R29") (pin "2") (pinfunction "2_2") (pintype "passive"))
      (node (ref "U2") (pin "17") (pinfunction "A8_17") (pintype "input"))
    )
    (net (code "24") (name "Net-(D10-K)") (class "Default")
      (node (ref "C10") (pin "1") (pinfunction "1_1") (pintype "passive"))
      (node (ref "D10") (pin "2") (pinfunction "K_2") (pintype "passive"))
      (node (ref "R27") (pin "2") (pinfunction "2_2") (pintype "passive"))
      (node (ref "U2") (pin "15") (pinfunction "A7_15") (pintype "input"))
    )
    (net (code "25") (name "Net-(D11-K)") (class "Default")
      (node (ref "C11") (pin "1") (pinfunction "1_1") (pintype "passive"))
      (node (ref "D11") (pin "2") (pinfunction "K_2") (pintype "passive"))
      (node (ref "R25") (pin "2") (pinfunction "2_2") (pintype "passive"))
      (node (ref "U2") (pin "13") (pinfunction "A6_13") (pintype "input"))
    )
    (net (code "26") (name "Net-(D12-K)") (class "Default")
      (node (ref "C12") (pin "1") (pinfunction "1_1") (pintype "passive"))
      (node (ref "D12") (pin "2") (pinfunction "K_2") (pintype "passive"))
      (node (ref "R23") (pin "2") (pinfunction "2_2") (pintype "passive"))
      (node (ref "U2") (pin "11") (pinfunction "A5_11") (pintype "input"))
    )
    (net (code "27") (name "Net-(D13-K)") (class "Default")
      (node (ref "C13") (pin "1") (pinfunction "1_1") (pintype "passive"))
      (node (ref "D13") (pin "2") (pinfunction "K_2") (pintype "passive"))
      (node (ref "R21") (pin "2") (pinfunction "2_2") (pintype "passive"))
      (node (ref "U2") (pin "8") (pinfunction "A4_8") (pintype "input"))
    )
    (net (code "28") (name "Net-(D14-K)") (class "Default")
      (node (ref "C14") (pin "1") (pinfunction "1_1") (pintype "passive"))
      (node (ref "D14") (pin "2") (pinfunction "K_2") (pintype "passive"))
      (node (ref "R19") (pin "2") (pinfunction "2_2") (pintype "passive"))
      (node (ref "U2") (pin "6") (pinfunction "A3_6") (pintype "input"))
    )
    (net (code "29") (name "Net-(D15-K)") (class "Default")
      (node (ref "C15") (pin "1") (pinfunction "1_1") (pintype "passive"))
      (node (ref "D15") (pin "2") (pinfunction "K_2") (pintype "passive"))
      (node (ref "R17") (pin "2") (pinfunction "2_2") (pintype "passive"))
      (node (ref "U2") (pin "4") (pinfunction "A2_4") (pintype "input"))
    )
    (net (code "30") (name "Net-(D16-K)") (class "Default")
      (node (ref "C16") (pin "1") (pinfunction "1_1") (pintype "passive"))
      (node (ref "D16") (pin "2") (pinfunction "K_2") (pintype "passive"))
      (node (ref "R15") (pin "2") (pinfunction "2_2") (pintype "passive"))
      (node (ref "U2") (pin "2") (pinfunction "A1_2") (pintype "input"))
    )
    (net (code "31") (name "Net-(D17-K)") (class "Default")
      (node (ref "C35") (pin "1") (pinfunction "1_1") (pintype "passive"))
      (node (ref "D17") (pin "2") (pinfunction "K_2") (pintype "passive"))
      (node (ref "R42") (pin "2") (pinfunction "2_2") (pintype "passive"))
      (node (ref "U5") (pin "2") (pinfunction "A1_2") (pintype "input"))
    )
    (net (code "32") (name "Net-(D18-K)") (class "Default")
      (node (ref "C36") (pin "1") (pinfunction "1_1") (pintype "passive"))
      (node (ref "D18") (pin "2") (pinfunction "K_2") (pintype "passive"))
      (node (ref "R44") (pin "2") (pinfunction "2_2") (pintype "passive"))
      (node (ref "U5") (pin "4") (pinfunction "A2_4") (pintype "input"))
    )
    (net (code "33") (name "Net-(D19-K)") (class "Default")
      (node (ref "C37") (pin "1") (pinfunction "1_1") (pintype "passive"))
      (node (ref "D19") (pin "2") (pinfunction "K_2") (pintype "passive"))
      (node (ref "R46") (pin "2") (pinfunction "2_2") (pintype "passive"))
      (node (ref "U5") (pin "6") (pinfunction "A3_6") (pintype "input"))
    )
    (net (code "34") (name "Net-(D20-K)") (class "Default")
      (node (ref "C38") (pin "1") (pinfunction "1_1") (pintype "passive"))
      (node (ref "D20") (pin "2") (pinfunction "K_2") (pintype "passive"))
      (node (ref "R48") (pin "2") (pinfunction "2_2") (pintype "passive"))
      (node (ref "U5") (pin "8") (pinfunction "A4_8") (pintype "input"))
    )
    (net (code "35") (name "Net-(D21-K)") (class "Default")
      (node (ref "C39") (pin "1") (pinfunction "1_1") (pintype "passive"))
      (node (ref "D21") (pin "2") (pinfunction "K_2") (pintype "passive"))
      (node (ref "R50") (pin "2") (pinfunction "2_2") (pintype "passive"))
      (node (ref "U5") (pin "11") (pinfunction "A5_11") (pintype "input"))
    )
    (net (code "36") (name "Net-(D22-K)") (class "Default")
      (node (ref "C40") (pin "1") (pinfunction "1_1") (pintype "passive"))
      (node (ref "D22") (pin "2") (pinfunction "K_2") (pintype "passive"))
      (node (ref "R52") (pin "2") (pinfunction "2_2") (pintype "passive"))
      (node (ref "U5") (pin "13") (pinfunction "A6_13") (pintype "input"))
    )
    (net (code "37") (name "Net-(D23-K)") (class "Default")
      (node (ref "C41") (pin "1") (pinfunction "1_1") (pintype "passive"))
      (node (ref "D23") (pin "2") (pinfunction "K_2") (pintype "passive"))
      (node (ref "R54") (pin "2") (pinfunction "2_2") (pintype "passive"))
      (node (ref "U5") (pin "15") (pinfunction "A7_15") (pintype "input"))
    )
    (net (code "38") (name "Net-(D24-K)") (class "Default")
      (node (ref "C42") (pin "1") (pinfunction "1_1") (pintype "passive"))
      (node (ref "D24") (pin "2") (pinfunction "K_2") (pintype "passive"))
      (node (ref "R56") (pin "2") (pinfunction "2_2") (pintype "passive"))
      (node (ref "U5") (pin "17") (pinfunction "A8_17") (pintype "input"))
    )
    (net (code "39") (name "Net-(D25-K)") (class "Default")
      (node (ref "C27") (pin "1") (pinfunction "1_1") (pintype "passive"))
      (node (ref "D25") (pin "2") (pinfunction "K_2") (pintype "passive"))
      (node (ref "R55") (pin "2") (pinfunction "2_2") (pintype "passive"))
      (node (ref "U4") (pin "17") (pinfunction "A8_17") (pintype "input"))
    )
    (net (code "40") (name "Net-(D26-K)") (class "Default")
      (node (ref "C28") (pin "1") (pinfunction "1_1") (pintype "passive"))
      (node (ref "D26") (pin "2") (pinfunction "K_2") (pintype "passive"))
      (node (ref "R53") (pin "2") (pinfunction "2_2") (pintype "passive"))
      (node (ref "U4") (pin "15") (pinfunction "A7_15") (pintype "input"))
    )
    (net (code "41") (name "Net-(D27-K)") (class "Default")
      (node (ref "C29") (pin "1") (pinfunction "1_1") (pintype "passive"))
      (node (ref "D27") (pin "2") (pinfunction "K_2") (pintype "passive"))
      (node (ref "R51") (pin "2") (pinfunction "2_2") (pintype "passive"))
      (node (ref "U4") (pin "13") (pinfunction "A6_13") (pintype "input"))
    )
    (net (code "42") (name "Net-(D28-K)") (class "Default")
      (node (ref "C30") (pin "1") (pinfunction "1_1") (pintype "passive"))
      (node (ref "D28") (pin "2") (pinfunction "K_2") (pintype "passive"))
      (node (ref "R49") (pin "2") (pinfunction "2_2") (pintype "passive"))
      (node (ref "U4") (pin "11") (pinfunction "A5_11") (pintype "input"))
    )
    (net (code "43") (name "Net-(D29-K)") (class "Default")
      (node (ref "C31") (pin "1") (pinfunction "1_1") (pintype "passive"))
      (node (ref "D29") (pin "2") (pinfunction "K_2") (pintype "passive"))
      (node (ref "R47") (pin "2") (pinfunction "2_2") (pintype "passive"))
      (node (ref "U4") (pin "8") (pinfunction "A4_8") (pintype "input"))
    )
    (net (code "44") (name "Net-(D30-K)") (class "Default")
      (node (ref "C32") (pin "1") (pinfunction "1_1") (pintype "passive"))
      (node (ref "D30") (pin "2") (pinfunction "K_2") (pintype "passive"))
      (node (ref "R45") (pin "2") (pinfunction "2_2") (pintype "passive"))
      (node (ref "U4") (pin "6") (pinfunction "A3_6") (pintype "input"))
    )
    (net (code "45") (name "Net-(D31-K)") (class "Default")
      (node (ref "C33") (pin "1") (pinfunction "1_1") (pintype "passive"))
      (node (ref "D31") (pin "2") (pinfunction "K_2") (pintype "passive"))
      (node (ref "R43") (pin "2") (pinfunction "2_2") (pintype "passive"))
      (node (ref "U4") (pin "4") (pinfunction "A2_4") (pintype "input"))
    )
    (net (code "46") (name "Net-(D32-K)") (class "Default")
      (node (ref "C34") (pin "1") (pinfunction "1_1") (pintype "passive"))
      (node (ref "D32") (pin "2") (pinfunction "K_2") (pintype "passive"))
      (node (ref "R41") (pin "2") (pinfunction "2_2") (pintype "passive"))
      (node (ref "U4") (pin "2") (pinfunction "A1_2") (pintype "input"))
    )
    (net (code "47") (name "Net-(P7-Pad1)") (class "Default")
      (node (ref "P7") (pin "1") (pinfunction "1_1") (pintype "passive"))
      (node (ref "R17") (pin "1") (pinfunction "1_1") (pintype "passive"))
    )
    (net (code "48") (name "Net-(P7-Pad2)") (class "Default")
      (node (ref "P7") (pin "2") (pinfunction "2_2") (pintype "passive"))
      (node (ref "R15") (pin "1") (pinfunction "1_1") (pintype "passive"))
    )
    (net (code "49") (name "Net-(P8-Pad1)") (class "Default")
      (node (ref "P8") (pin "1") (pinfunction "1_1") (pintype "passive"))
      (node (ref "R18") (pin "1") (pinfunction "1_1") (pintype "passive"))
    )
    (net (code "50") (name "Net-(P8-Pad2)") (class "Default")
      (node (ref "P8") (pin "2") (pinfunction "2_2") (pintype "passive"))
      (node (ref "R16") (pin "1") (pinfunction "1_1") (pintype "passive"))
    )
    (net (code "51") (name "Net-(P9-Pad1)") (class "Default")
      (node (ref "P9") (pin "1") (pinfunction "1_1") (pintype "passive"))
      (node (ref "R21") (pin "1") (pinfunction "1_1") (pintype "passive"))
    )
    (net (code "52") (name "Net-(P9-Pad2)") (class "Default")
      (node (ref "P9") (pin "2") (pinfunction "2_2") (pintype "passive"))
      (node (ref "R19") (pin "1") (pinfunction "1_1") (pintype "passive"))
    )
    (net (code "53") (name "Net-(P10-Pad1)") (class "Default")
      (node (ref "P10") (pin "1") (pinfunction "1_1") (pintype "passive"))
      (node (ref "R22") (pin "1") (pinfunction "1_1") (pintype "passive"))
    )
    (net (code "54") (name "Net-(P10-Pad2)") (class "Default")
      (node (ref "P10") (pin "2") (pinfunction "2_2") (pintype "passive"))
      (node (ref "R20") (pin "1") (pinfunction "1_1") (pintype "passive"))
    )
    (net (code "55") (name "Net-(P11-Pad1)") (class "Default")
      (node (ref "P11") (pin "1") (pinfunction "1_1") (pintype "passive"))
      (node (ref "R25") (pin "1") (pinfunction "1_1") (pintype "passive"))
    )
    (net (code "56") (name "Net-(P11-Pad2)") (class "Default")
      (node (ref "P11") (pin "2") (pinfunction "2_2") (pintype "passive"))
      (node (ref "R23") (pin "1") (pinfunction "1_1") (pintype "passive"))
    )
    (net (code "57") (name "Net-(P12-Pad1)") (class "Default")
      (node (ref "P12") (pin "1") (pinfunction "1_1") (pintype "passive"))
      (node (ref "R26") (pin "1") (pinfunction "1_1") (pintype "passive"))
    )
    (net (code "58") (name "Net-(P12-Pad2)") (class "Default")
      (node (ref "P12") (pin "2") (pinfunction "2_2") (pintype "passive"))
      (node (ref "R24") (pin "1") (pinfunction "1_1") (pintype "passive"))
    )
    (net (code "59") (name "Net-(P13-Pad1)") (class "Default")
      (node (ref "P13") (pin "1") (pinfunction "1_1") (pintype "passive"))
      (node (ref "R29") (pin "1") (pinfunction "1_1") (pintype "passive"))
    )
    (net (code "60") (name "Net-(P13-Pad2)") (class "Default")
      (node (ref "P13") (pin "2") (pinfunction "2_2") (pintype "passive"))
      (node (ref "R27") (pin "1") (pinfunction "1_1") (pintype "passive"))
    )
    (net (code "61") (name "Net-(P14-Pad1)") (class "Default")
      (node (ref "P14") (pin "1") (pinfunction "1_1") (pintype "passive"))
      (node (ref "R30") (pin "1") (pinfunction "1_1") (pintype "passive"))
    )
    (net (code "62") (name "Net-(P14-Pad2)") (class "Default")
      (node (ref "P14") (pin "2") (pinfunction "2_2") (pintype "passive"))
      (node (ref "R28") (pin "1") (pinfunction "1_1") (pintype "passive"))
    )
    (net (code "63") (name "Net-(P15-Pad1)") (class "Default")
      (node (ref "P15") (pin "1") (pinfunction "1_1") (pintype "passive"))
      (node (ref "R37") (pin "2") (pinfunction "2_2") (pintype "passive"))
      (node (ref "R38") (pin "2") (pinfunction "2_2") (pintype "passive"))
    )
    (net (code "64") (name "Net-(P15-Pad2)") (class "Default")
      (node (ref "P15") (pin "2") (pinfunction "2_2") (pintype "passive"))
      (node (ref "R33") (pin "1") (pinfunction "1_1") (pintype "passive"))
      (node (ref "R34") (pin "1") (pinfunction "1_1") (pintype "passive"))
    )
    (net (code "65") (name "Net-(P16-Pad1)") (class "Default")
      (node (ref "P16") (pin "1") (pinfunction "1_1") (pintype "passive"))
      (node (ref "R35") (pin "2") (pinfunction "2_2") (pintype "passive"))
      (node (ref "R36") (pin "2") (pinfunction "2_2") (pintype "passive"))
    )
    (net (code "66") (name "Net-(P16-Pad2)") (class "Default")
      (node (ref "P16") (pin "2") (pinfunction "2_2") (pintype "passive"))
      (node (ref "R31") (pin "1") (pinfunction "1_1") (pintype "passive"))
      (node (ref "R32") (pin "1") (pinfunction "1_1") (pintype "passive"))
    )
    (net (code "67") (name "Net-(P17-Pad1)") (class "Default")
      (node (ref "P17") (pin "1") (pinfunction "1_1") (pintype "passive"))
      (node (ref "R43") (pin "1") (pinfunction "1_1") (pintype "passive"))
    )
    (net (code "68") (name "Net-(P17-Pad2)") (class "Default")
      (node (ref "P17") (pin "2") (pinfunction "2_2") (pintype "passive"))
      (node (ref "R41") (pin "1") (pinfunction "1_1") (pintype "passive"))
    )
    (net (code "69") (name "Net-(P18-Pad1)") (class "Default")
      (node (ref "P18") (pin "1") (pinfunction "1_1") (pintype "passive"))
      (node (ref "R44") (pin "1") (pinfunction "1_1") (pintype "passive"))
    )
    (net (code "70") (name "Net-(P18-Pad2)") (class "Default")
      (node (ref "P18") (pin "2") (pinfunction "2_2") (pintype "passive"))
      (node (ref "R42") (pin "1") (pinfunction "1_1") (pintype "passive"))
    )
    (net (code "71") (name "Net-(P19-Pad1)") (class "Default")
      (node (ref "P19") (pin "1") (pinfunction "1_1") (pintype "passive"))
      (node (ref "R47") (pin "1") (pinfunction "1_1") (pintype "passive"))
    )
    (net (code "72") (name "Net-(P19-Pad2)") (class "Default")
      (node (ref "P19") (pin "2") (pinfunction "2_2") (pintype "passive"))
      (node (ref "R45") (pin "1") (pinfunction "1_1") (pintype "passive"))
    )
    (net (code "73") (name "Net-(P20-Pad1)") (class "Default")
      (node (ref "P20") (pin "1") (pinfunction "1_1") (pintype "passive"))
      (node (ref "R48") (pin "1") (pinfunction "1_1") (pintype "passive"))
    )
    (net (code "74") (name "Net-(P20-Pad2)") (class "Default")
      (node (ref "P20") (pin "2") (pinfunction "2_2") (pintype "passive"))
      (node (ref "R46") (pin "1") (pinfunction "1_1") (pintype "passive"))
    )
    (net (code "75") (name "Net-(P21-Pad1)") (class "Default")
      (node (ref "P21") (pin "1") (pinfunction "1_1") (pintype "passive"))
      (node (ref "R51") (pin "1") (pinfunction "1_1") (pintype "passive"))
    )
    (net (code "76") (name "Net-(P21-Pad2)") (class "Default")
      (node (ref "P21") (pin "2") (pinfunction "2_2") (pintype "passive"))
      (node (ref "R49") (pin "1") (pinfunction "1_1") (pintype "passive"))
    )
    (net (code "77") (name "Net-(P22-Pad1)") (class "Default")
      (node (ref "P22") (pin "1") (pinfunction "1_1") (pintype "passive"))
      (node (ref "R52") (pin "1") (pinfunction "1_1") (pintype "passive"))
    )
    (net (code "78") (name "Net-(P22-Pad2)") (class "Default")
      (node (ref "P22") (pin "2") (pinfunction "2_2") (pintype "passive"))
      (node (ref "R50") (pin "1") (pinfunction "1_1") (pintype "passive"))
    )
    (net (code "79") (name "Net-(P23-Pad1)") (class "Default")
      (node (ref "P23") (pin "1") (pinfunction "1_1") (pintype "passive"))
      (node (ref "R55") (pin "1") (pinfunction "1_1") (pintype "passive"))
    )
    (net (code "80") (name "Net-(P23-Pad2)") (class "Default")
      (node (ref "P23") (pin "2") (pinfunction "2_2") (pintype "passive"))
      (node (ref "R53") (pin "1") (pinfunction "1_1") (pintype "passive"))
    )
    (net (code "81") (name "Net-(P24-Pad1)") (class "Default")
      (node (ref "P24") (pin "1") (pinfunction "1_1") (pintype "passive"))
      (node (ref "R56") (pin "1") (pinfunction "1_1") (pintype "passive"))
    )
    (net (code "82") (name "Net-(P24-Pad2)") (class "Default")
      (node (ref "P24") (pin "2") (pinfunction "2_2") (pintype "passive"))
      (node (ref "R54") (pin "1") (pinfunction "1_1") (pintype "passive"))
    )
    (net (code "83") (name "VSS") (class "Default")
      (node (ref "C10") (pin "2") (pinfunction "2_2") (pintype "passive"))
      (node (ref "C11") (pin "2") (pinfunction "2_2") (pintype "passive"))
      (node (ref "C12") (pin "2") (pinfunction "2_2") (pintype "passive"))
      (node (ref "C13") (pin "2") (pinfunction "2_2") (pintype "passive"))
      (node (ref "C14") (pin "2") (pinfunction "2_2") (pintype "passive"))
      (node (ref "C15") (pin "2") (pinfunction "2_2") (pintype "passive"))
      (node (ref "C16") (pin "2") (pinfunction "2_2") (pintype "passive"))
      (node (ref "C17") (pin "2") (pinfunction "2_2") (pintype "passive"))
      (node (ref "C18") (pin "2") (pinfunction "2_2") (pintype "passive"))
      (node (ref "C19") (pin "2") (pinfunction "2_2") (pintype "passive"))
      (node (ref "C20") (pin "2") (pinfunction "2_2") (pintype "passive"))
      (node (ref "C21") (pin "2") (pinfunction "2_2") (pintype "passive"))
      (node (ref "C22") (pin "2") (pinfunction "2_2") (pintype "passive"))
      (node (ref "C23") (pin "2") (pinfunction "2_2") (pintype "passive"))
      (node (ref "C24") (pin "2") (pinfunction "2_2") (pintype "passive"))
      (node (ref "C25") (pin "2") (pinfunction "2_2") (pintype "passive"))
      (node (ref "C26") (pin "2") (pinfunction "2_2") (pintype "passive"))
      (node (ref "C27") (pin "2") (pinfunction "2_2") (pintype "passive"))
      (node (ref "C28") (pin "2") (pinfunction "2_2") (pintype "passive"))
      (node (ref "C29") (pin "2") (pinfunction "2_2") (pintype "passive"))
      (node (ref "C30") (pin "2") (pinfunction "2_2") (pintype "passive"))
      (node (ref "C31") (pin "2") (pinfunction "2_2") (pintype "passive"))
      (node (ref "C32") (pin "2") (pinfunction "2_2") (pintype "passive"))
      (node (ref "C33") (pin "2") (pinfunction "2_2") (pintype "passive"))
      (node (ref "C34") (pin "2") (pinfunction "2_2") (pintype "passive"))
      (node (ref "C35") (pin "2") (pinfunction "2_2") (pintype "passive"))
      (node (ref "C36") (pin "2") (pinfunction "2_2") (pintype "passive"))
      (node (ref "C37") (pin "2") (pinfunction "2_2") (pintype "passive"))
      (node (ref "C38") (pin "2") (pinfunction "2_2") (pintype "passive"))
      (node (ref "C39") (pin "2") (pinfunction "2_2") (pintype "passive"))
      (node (ref "C40") (pin "2") (pinfunction "2_2") (pintype "passive"))
      (node (ref "C41") (pin "2") (pinfunction "2_2") (pintype "passive"))
      (node (ref "C42") (pin "2") (pinfunction "2_2") (pintype "passive"))
      (node (ref "C7") (pin "2") (pinfunction "2_2") (pintype "passive"))
      (node (ref "C8") (pin "2") (pinfunction "2_2") (pintype "passive"))
      (node (ref "C9") (pin "2") (pinfunction "2_2") (pintype "passive"))
      (node (ref "D1") (pin "1") (pinfunction "A_1") (pintype "passive"))
      (node (ref "D10") (pin "1") (pinfunction "A_1") (pintype "passive"))
      (node (ref "D11") (pin "1") (pinfunction "A_1") (pintype "passive"))
      (node (ref "D12") (pin "1") (pinfunction "A_1") (pintype "passive"))
      (node (ref "D13") (pin "1") (pinfunction "A_1") (pintype "passive"))
      (node (ref "D14") (pin "1") (pinfunction "A_1") (pintype "passive"))
      (node (ref "D15") (pin "1") (pinfunction "A_1") (pintype "passive"))
      (node (ref "D16") (pin "1") (pinfunction "A_1") (pintype "passive"))
      (node (ref "D17") (pin "1") (pinfunction "A_1") (pintype "passive"))
      (node (ref "D18") (pin "1") (pinfunction "A_1") (pintype "passive"))
      (node (ref "D19") (pin "1") (pinfunction "A_1") (pintype "passive"))
      (node (ref "D2") (pin "1") (pinfunction "A_1") (pintype "passive"))
      (node (ref "D20") (pin "1") (pinfunction "A_1") (pintype "passive"))
      (node (ref "D21") (pin "1") (pinfunction "A_1") (pintype "passive"))
      (node (ref "D22") (pin "1") (pinfunction "A_1") (pintype "passive"))
      (node (ref "D23") (pin "1") (pinfunction "A_1") (pintype "passive"))
      (node (ref "D24") (pin "1") (pinfunction "A_1") (pintype "passive"))
      (node (ref "D25") (pin "1") (pinfunction "A_1") (pintype "passive"))
      (node (ref "D26") (pin "1") (pinfunction "A_1") (pintype "passive"))
      (node (ref "D27") (pin "1") (pinfunction "A_1") (pintype "passive"))
      (node (ref "D28") (pin "1") (pinfunction "A_1") (pintype "passive"))
      (node (ref "D29") (pin "1") (pinfunction "A_1") (pintype "passive"))
      (node (ref "D3") (pin "1") (pinfunction "A_1") (pintype "passive"))
      (node (ref "D30") (pin "1") (pinfunction "A_1") (pintype "passive"))
      (node (ref "D31") (pin "1") (pinfunction "A_1") (pintype "passive"))
      (node (ref "D32") (pin "1") (pinfunction "A_1") (pintype "passive"))
      (node (ref "D4") (pin "1") (pinfunction "A_1") (pintype "passive"))
      (node (ref "D5") (pin "1") (pinfunction "A_1") (pintype "passive"))
      (node (ref "D6") (pin "1") (pinfunction "A_1") (pintype "passive"))
      (node (ref "D7") (pin "1") (pinfunction "A_1") (pintype "passive"))
      (node (ref "D8") (pin "1") (pinfunction "A_1") (pintype "passive"))
      (node (ref "D9") (pin "1") (pinfunction "A_1") (pintype "passive"))
      (node (ref "R35") (pin "1") (pinfunction "1_1") (pintype "passive"))
      (node (ref "R36") (pin "1") (pinfunction "1_1") (pintype "passive"))
      (node (ref "R37") (pin "1") (pinfunction "1_1") (pintype "passive"))
      (node (ref "R38") (pin "1") (pinfunction "1_1") (pintype "passive"))
      (node (ref "U2") (pin "10") (pinfunction "GND_10") (pintype "power_in"))
      (node (ref "U3") (pin "10") (pinfunction "GND_10") (pintype "power_in"))
      (node (ref "U4") (pin "10") (pinfunction "GND_10") (pintype "power_in"))
      (node (ref "U5") (pin "10") (pinfunction "GND_10") (pintype "power_in"))
    )
  )
)
